# PS4-sequencer.net
KiCad netlist of a schematic drawn in EAGLE
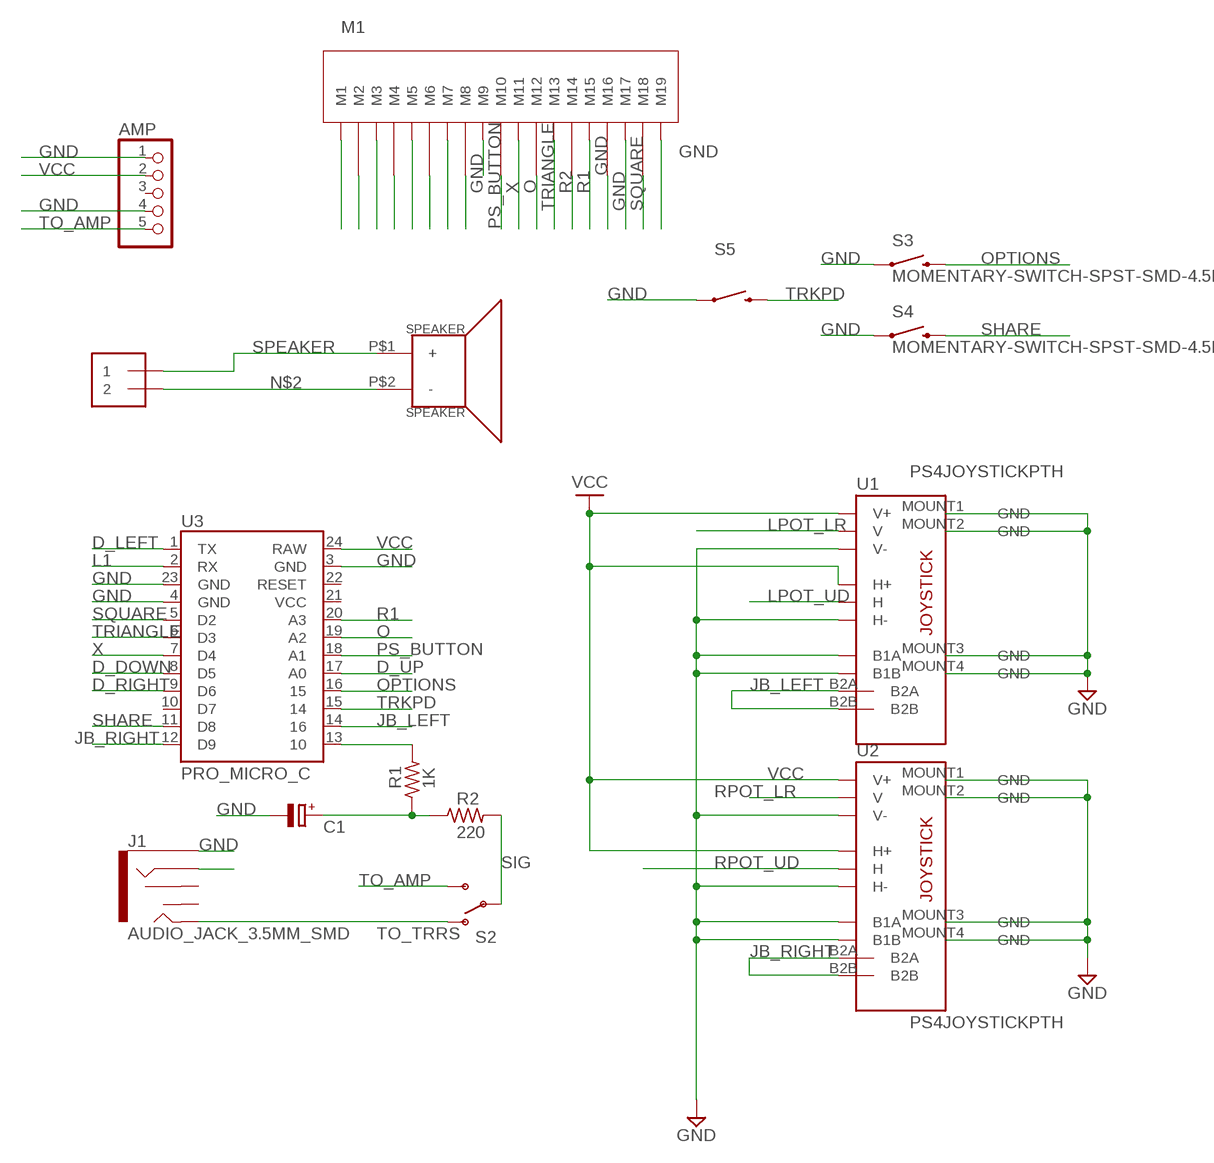
[diagram p0: schematic, sheet 1]

(export (version "E")
  (design (tool "Eeschema 10.0.6"))
  (components
    (comp (ref "AMP")
      (value "PINHD-1X5")
      (footprint "eagle-import:1X05")
      (libsource (lib "eagle-import") (part "PINHD-1X5"))
    )
    (comp (ref "C1")
      (value "CAPACITOR-POLRADIAL-5MM-DIA")
      (footprint "eagle-import:CAPPRD254W65D500H1150B")
      (libsource (lib "eagle-import") (part "CAPACITOR-POLRADIAL-5MM-DIA"))
    )
    (comp (ref "J1")
      (value "AUDIO_JACK_3.5MM_SMD")
      (footprint "eagle-import:AUDIO-JACK-3.5MM-SMD")
      (libsource (lib "eagle-import") (part "AUDIO_JACK_3.5MM_SMD"))
    )
    (comp (ref "J2")
      (value "1X2-3.5MM")
      (footprint "eagle-import:1X2-3.5MM")
      (libsource (lib "eagle-import") (part "1X2-3.5MM"))
    )
    (comp (ref "M1")
      (value "PS4MEMBRANE")
      (footprint "eagle-import:PS4MEMBRANE")
      (libsource (lib "eagle-import") (part "PS4MEMBRANE"))
    )
    (comp (ref "R1")
      (value "1K")
      (footprint "eagle-import:RESAD724W46L381D178B")
      (libsource (lib "eagle-import") (part "R-USAXIAL-7.2MM-PITCH_"))
    )
    (comp (ref "R2")
      (value "220")
      (footprint "eagle-import:RESAD724W46L381D178B")
      (libsource (lib "eagle-import") (part "R-USAXIAL-7.2MM-PITCH_"))
    )
    (comp (ref "S2")
      (value "SWITCH-SPDTSMD")
      (footprint "eagle-import:SWITCH_SPDT_SMD")
      (libsource (lib "eagle-import") (part "SWITCH-SPDTSMD"))
    )
    (comp (ref "S3")
      (value "MOMENTARY-SWITCH-SPST-SMD-4.5MM")
      (footprint "eagle-import:TACTILE_SWITCH_SMD_3.6MM")
      (libsource (lib "eagle-import") (part "MOMENTARY-SWITCH-SPST-SMD-4.5MM"))
    )
    (comp (ref "S4")
      (value "MOMENTARY-SWITCH-SPST-SMD-4.5MM")
      (footprint "eagle-import:TACTILE_SWITCH_SMD_3.6MM")
      (libsource (lib "eagle-import") (part "MOMENTARY-SWITCH-SPST-SMD-4.5MM"))
    )
    (comp (ref "S5")
      (value "TAC_SWITCHSMD")
      (footprint "eagle-import:TACTILE_SWITCH_SMD_6MM")
      (libsource (lib "eagle-import") (part "MOMENTARY-SWITCH-SPST-SMD-5.2MM"))
    )
    (comp (ref "SPEAKER")
      (value "SPEAKER")
      (footprint "eagle-import:PS4_SPEAKER")
      (libsource (lib "eagle-import") (part "SPEAKER"))
    )
    (comp (ref "U1")
      (value "PS4JOYSTICKPTH")
      (footprint "eagle-import:PS4JOYSTICK")
      (libsource (lib "eagle-import") (part "PS4JOYSTICKPTH"))
    )
    (comp (ref "U2")
      (value "PS4JOYSTICKPTH")
      (footprint "eagle-import:PS4JOYSTICK")
      (libsource (lib "eagle-import") (part "PS4JOYSTICKPTH"))
    )
    (comp (ref "U3")
      (value "PRO_MICRO_C")
      (footprint "eagle-import:PRO_MICRO_C")
      (libsource (lib "eagle-import") (part "PRO_MICRO_C"))
    )
  )
  (nets
    (net (code "1") (name "/D_DOWN") (class "Default")
      (node (ref "M1") (pin "8") (pinfunction "M8_8") (pintype "bidirectional"))
      (node (ref "U3") (pin "8") (pinfunction "D5_8") (pintype "bidirectional"))
    )
    (net (code "2") (name "/D_LEFT") (class "Default")
      (node (ref "M1") (pin "7") (pinfunction "M7_7") (pintype "bidirectional"))
      (node (ref "U3") (pin "1") (pinfunction "TX_1") (pintype "bidirectional"))
    )
    (net (code "3") (name "/D_RIGHT") (class "Default")
      (node (ref "M1") (pin "5") (pinfunction "M5_5") (pintype "bidirectional"))
      (node (ref "U3") (pin "9") (pinfunction "D6_9") (pintype "bidirectional"))
    )
    (net (code "4") (name "/D_UP") (class "Default")
      (node (ref "M1") (pin "6") (pinfunction "M6_6") (pintype "bidirectional"))
      (node (ref "U3") (pin "17") (pinfunction "A0_17") (pintype "bidirectional"))
    )
    (net (code "5") (name "/JB_LEFT") (class "Default")
      (node (ref "U1") (pin "B2A") (pinfunction "B2A_B2A") (pintype "bidirectional"))
      (node (ref "U1") (pin "B2B") (pinfunction "B2B_B2B") (pintype "bidirectional"))
      (node (ref "U3") (pin "14") (pinfunction "16_14") (pintype "bidirectional"))
    )
    (net (code "6") (name "/JB_RIGHT") (class "Default")
      (node (ref "U2") (pin "B2A") (pinfunction "B2A_B2A") (pintype "bidirectional"))
      (node (ref "U2") (pin "B2B") (pinfunction "B2B_B2B") (pintype "bidirectional"))
      (node (ref "U3") (pin "12") (pinfunction "D9_12") (pintype "bidirectional"))
    )
    (net (code "7") (name "/L1") (class "Default")
      (node (ref "M1") (pin "2") (pinfunction "M2_2") (pintype "power_in"))
      (node (ref "U3") (pin "2") (pinfunction "RX_2") (pintype "bidirectional"))
    )
    (net (code "8") (name "/LPOT_LR") (class "Default")
      (node (ref "U1") (pin "V2") (pinfunction "V_V2") (pintype "bidirectional"))
    )
    (net (code "9") (name "/LPOT_UD") (class "Default")
      (node (ref "U1") (pin "H2") (pinfunction "H_H2") (pintype "bidirectional"))
    )
    (net (code "10") (name "/N$2") (class "Default")
      (node (ref "J2") (pin "2") (pinfunction "2_2") (pintype "passive"))
      (node (ref "SPEAKER") (pin "P$2") (pinfunction "-_P$2") (pintype "bidirectional"))
    )
    (net (code "11") (name "/O") (class "Default")
      (node (ref "M1") (pin "12") (pinfunction "M12_12") (pintype "bidirectional"))
      (node (ref "U3") (pin "19") (pinfunction "A2_19") (pintype "bidirectional"))
    )
    (net (code "12") (name "/OPTIONS") (class "Default")
      (node (ref "S3") (pin "1") (pinfunction "2_1") (pintype "passive"))
      (node (ref "S3") (pin "4") (pinfunction "2_4") (pintype "passive"))
      (node (ref "U3") (pin "16") (pinfunction "15_16") (pintype "bidirectional"))
    )
    (net (code "13") (name "/PS_BUTTON") (class "Default")
      (node (ref "M1") (pin "10") (pinfunction "M10_10") (pintype "power_in"))
      (node (ref "U3") (pin "18") (pinfunction "A1_18") (pintype "bidirectional"))
    )
    (net (code "14") (name "/R1") (class "Default")
      (node (ref "M1") (pin "15") (pinfunction "M15_15") (pintype "bidirectional"))
      (node (ref "U3") (pin "20") (pinfunction "A3_20") (pintype "bidirectional"))
    )
    (net (code "15") (name "/R2") (class "Default")
      (node (ref "M1") (pin "14") (pinfunction "M14_14") (pintype "bidirectional"))
    )
    (net (code "16") (name "/RPOT_LR") (class "Default")
      (node (ref "U2") (pin "V2") (pinfunction "V_V2") (pintype "bidirectional"))
    )
    (net (code "17") (name "/RPOT_UD") (class "Default")
      (node (ref "U2") (pin "H2") (pinfunction "H_H2") (pintype "bidirectional"))
    )
    (net (code "18") (name "/SHARE") (class "Default")
      (node (ref "S4") (pin "1") (pinfunction "2_1") (pintype "passive"))
      (node (ref "S4") (pin "4") (pinfunction "2_4") (pintype "passive"))
      (node (ref "U3") (pin "11") (pinfunction "D8_11") (pintype "bidirectional"))
    )
    (net (code "19") (name "/SIG") (class "Default")
      (node (ref "R2") (pin "2") (pinfunction "2_2") (pintype "passive"))
      (node (ref "S2") (pin "2") (pinfunction "P_2") (pintype "passive"))
    )
    (net (code "20") (name "/SPEAKER") (class "Default")
      (node (ref "J2") (pin "1") (pinfunction "1_1") (pintype "passive"))
      (node (ref "SPEAKER") (pin "P$1") (pinfunction "+_P$1") (pintype "bidirectional"))
    )
    (net (code "21") (name "/SQUARE") (class "Default")
      (node (ref "M1") (pin "18") (pinfunction "M18_18") (pintype "bidirectional"))
      (node (ref "U3") (pin "5") (pinfunction "D2_5") (pintype "bidirectional"))
    )
    (net (code "22") (name "/TO_AMP") (class "Default")
      (node (ref "AMP") (pin "5") (pinfunction "5_5") (pintype "passive"))
      (node (ref "S2") (pin "3") (pinfunction "S_3") (pintype "passive"))
    )
    (net (code "23") (name "/TO_TRRS") (class "Default")
      (node (ref "J1") (pin "TIP") (pinfunction "TIP_TIP") (pintype "bidirectional"))
      (node (ref "S2") (pin "1") (pinfunction "O_1") (pintype "passive"))
    )
    (net (code "24") (name "/TRIANGLE") (class "Default")
      (node (ref "M1") (pin "13") (pinfunction "M13_13") (pintype "bidirectional"))
      (node (ref "U3") (pin "6") (pinfunction "D3_6") (pintype "bidirectional"))
    )
    (net (code "25") (name "/TRKPD") (class "Default")
      (node (ref "S5") (pin "3") (pinfunction "2_3") (pintype "passive"))
      (node (ref "U3") (pin "15") (pinfunction "14_15") (pintype "bidirectional"))
    )
    (net (code "26") (name "/X") (class "Default")
      (node (ref "M1") (pin "11") (pinfunction "M11_11") (pintype "bidirectional"))
      (node (ref "U3") (pin "7") (pinfunction "D4_7") (pintype "bidirectional"))
    )
    (net (code "27") (name "GND") (class "Default")
      (node (ref "AMP") (pin "1") (pinfunction "1_1") (pintype "passive"))
      (node (ref "AMP") (pin "4") (pinfunction "4_4") (pintype "passive"))
      (node (ref "C1") (pin "2") (pinfunction "-_2") (pintype "passive"))
      (node (ref "J1") (pin "SLEEVE") (pinfunction "SLEEVE_SLEEVE") (pintype "bidirectional"))
      (node (ref "M1") (pin "16") (pinfunction "M16_16") (pintype "bidirectional"))
      (node (ref "M1") (pin "17") (pinfunction "M17_17") (pintype "bidirectional"))
      (node (ref "M1") (pin "19") (pinfunction "M19_19") (pintype "bidirectional"))
      (node (ref "M1") (pin "3") (pinfunction "M3_3") (pintype "power_in"))
      (node (ref "M1") (pin "9") (pinfunction "M9_9") (pintype "power_in"))
      (node (ref "S3") (pin "2") (pinfunction "1_2") (pintype "passive"))
      (node (ref "S3") (pin "3") (pinfunction "1_3") (pintype "passive"))
      (node (ref "S4") (pin "2") (pinfunction "1_2") (pintype "passive"))
      (node (ref "S4") (pin "3") (pinfunction "1_3") (pintype "passive"))
      (node (ref "S5") (pin "1") (pinfunction "1_1") (pintype "passive"))
      (node (ref "U1") (pin "B1A") (pinfunction "B1A_B1A") (pintype "bidirectional"))
      (node (ref "U1") (pin "B1B") (pinfunction "B1B_B1B") (pintype "bidirectional"))
      (node (ref "U1") (pin "H3") (pinfunction "H-_H3") (pintype "bidirectional"))
      (node (ref "U1") (pin "MOUNT1") (pinfunction "GND_MOUNT1") (pintype "bidirectional"))
      (node (ref "U1") (pin "MOUNT2") (pinfunction "GND_MOUNT2") (pintype "bidirectional"))
      (node (ref "U1") (pin "MOUNT3") (pinfunction "GND_MOUNT3") (pintype "bidirectional"))
      (node (ref "U1") (pin "MOUNT4") (pinfunction "GND_MOUNT4") (pintype "bidirectional"))
      (node (ref "U1") (pin "V3") (pinfunction "V-_V3") (pintype "bidirectional"))
      (node (ref "U2") (pin "B1A") (pinfunction "B1A_B1A") (pintype "bidirectional"))
      (node (ref "U2") (pin "B1B") (pinfunction "B1B_B1B") (pintype "bidirectional"))
      (node (ref "U2") (pin "H3") (pinfunction "H-_H3") (pintype "bidirectional"))
      (node (ref "U2") (pin "MOUNT1") (pinfunction "GND_MOUNT1") (pintype "bidirectional"))
      (node (ref "U2") (pin "MOUNT2") (pinfunction "GND_MOUNT2") (pintype "bidirectional"))
      (node (ref "U2") (pin "MOUNT3") (pinfunction "GND_MOUNT3") (pintype "bidirectional"))
      (node (ref "U2") (pin "MOUNT4") (pinfunction "GND_MOUNT4") (pintype "bidirectional"))
      (node (ref "U2") (pin "V3") (pinfunction "V-_V3") (pintype "bidirectional"))
      (node (ref "U3") (pin "23") (pinfunction "GND_23") (pintype "bidirectional"))
      (node (ref "U3") (pin "3") (pinfunction "GND_3") (pintype "bidirectional"))
      (node (ref "U3") (pin "4") (pinfunction "GND_4") (pintype "bidirectional"))
    )
    (net (code "28") (name "Net-(C1-+)") (class "Default")
      (node (ref "C1") (pin "1") (pinfunction "+_1") (pintype "passive"))
      (node (ref "R1") (pin "1") (pinfunction "1_1") (pintype "passive"))
      (node (ref "R2") (pin "1") (pinfunction "1_1") (pintype "passive"))
    )
    (net (code "29") (name "Net-(U3-10)") (class "Default")
      (node (ref "R1") (pin "2") (pinfunction "2_2") (pintype "passive"))
      (node (ref "U3") (pin "13") (pinfunction "10_13") (pintype "bidirectional"))
    )
    (net (code "30") (name "VCC") (class "Default")
      (node (ref "AMP") (pin "2") (pinfunction "2_2") (pintype "passive"))
      (node (ref "U1") (pin "H1") (pinfunction "H+_H1") (pintype "bidirectional"))
      (node (ref "U1") (pin "V1") (pinfunction "V+_V1") (pintype "bidirectional"))
      (node (ref "U2") (pin "H1") (pinfunction "H+_H1") (pintype "bidirectional"))
      (node (ref "U2") (pin "V1") (pinfunction "V+_V1") (pintype "bidirectional"))
      (node (ref "U3") (pin "24") (pinfunction "RAW_24") (pintype "bidirectional"))
    )
    (net (code "31") (name "unconnected-(AMP-Pad3)") (class "Default")
      (node (ref "AMP") (pin "3") (pinfunction "3_3") (pintype "passive"))
    )
    (net (code "32") (name "unconnected-(J1-PadRSH)") (class "Default")
      (node (ref "J1") (pin "RSH") (pinfunction "RSH_RSH") (pintype "bidirectional"))
    )
    (net (code "33") (name "unconnected-(J1-PadTSH)") (class "Default")
      (node (ref "J1") (pin "TSH") (pinfunction "TSH_TSH") (pintype "bidirectional"))
    )
    (net (code "34") (name "unconnected-(J1-RING-PadRING1)") (class "Default")
      (node (ref "J1") (pin "RING1") (pinfunction "RING_RING1") (pintype "bidirectional"))
    )
    (net (code "35") (name "unconnected-(M1-M1-Pad1)") (class "Default")
      (node (ref "M1") (pin "1") (pinfunction "M1_1") (pintype "bidirectional"))
    )
    (net (code "36") (name "unconnected-(M1-M4-Pad4)") (class "Default")
      (node (ref "M1") (pin "4") (pinfunction "M4_4") (pintype "bidirectional"))
    )
    (net (code "37") (name "unconnected-(U3-D7-Pad10)") (class "Default")
      (node (ref "U3") (pin "10") (pinfunction "D7_10") (pintype "bidirectional"))
    )
    (net (code "38") (name "unconnected-(U3-RESET-Pad22)") (class "Default")
      (node (ref "U3") (pin "22") (pinfunction "RESET_22") (pintype "bidirectional"))
    )
    (net (code "39") (name "unconnected-(U3-VCC-Pad21)") (class "Default")
      (node (ref "U3") (pin "21") (pinfunction "VCC_21") (pintype "bidirectional"))
    )
  )
)
